# tinyK20.net
KiCad netlist of a schematic drawn in EAGLE
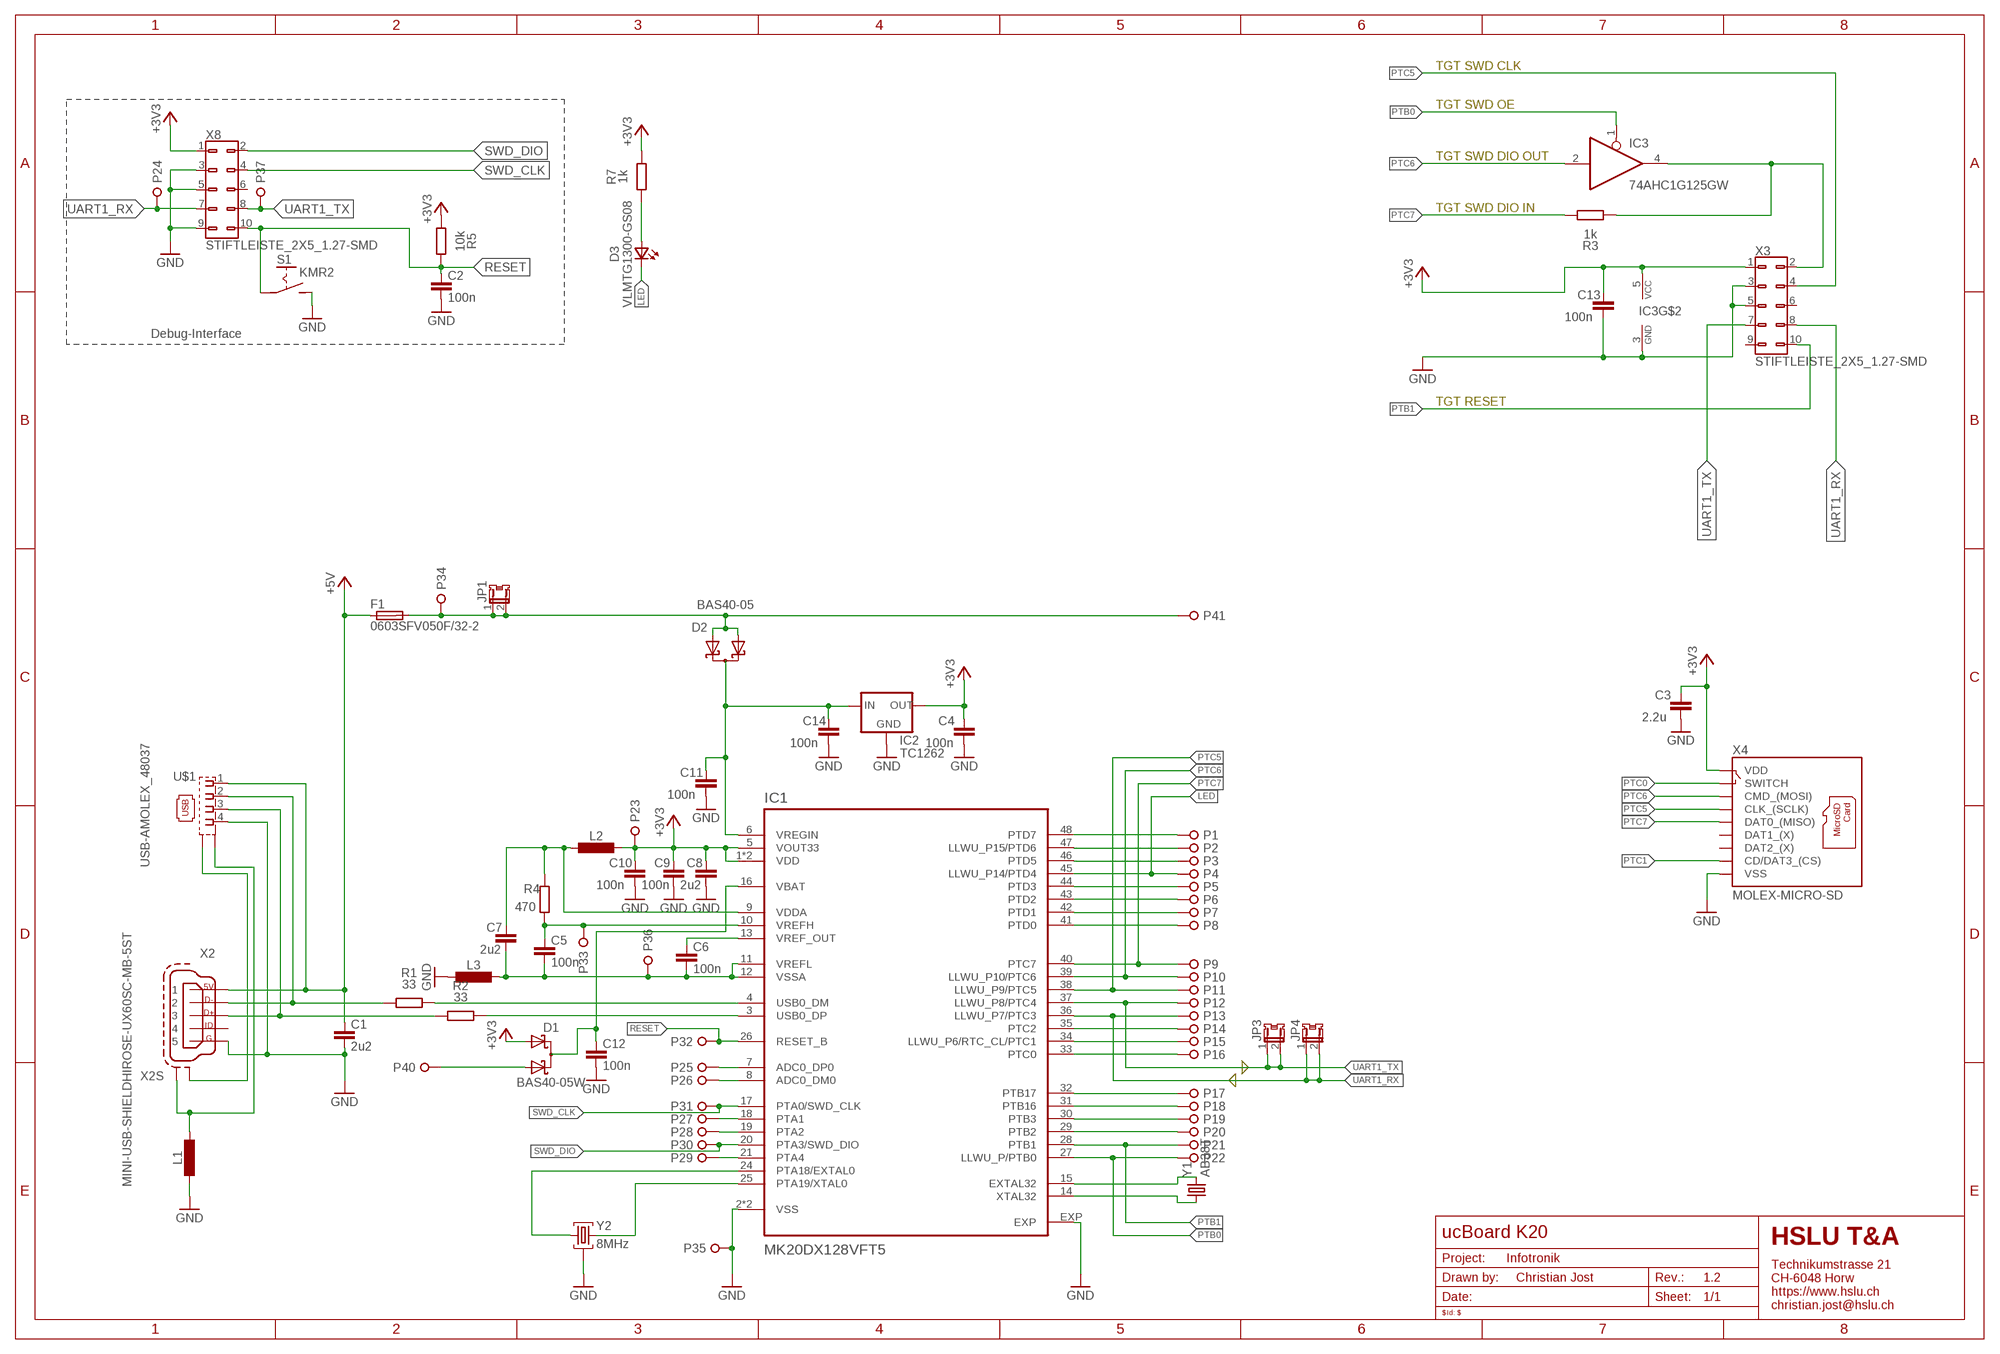
[diagram p0: schematic, sheet 1]

(export (version "E")
  (design (tool "Eeschema 10.0.6"))
  (components
    (comp (ref "C1")
      (value "2u2")
      (footprint "eagle-import:C0603-R")
      (libsource (lib "eagle-import") (part "C0603"))
    )
    (comp (ref "C2")
      (value "100n")
      (footprint "eagle-import:C0603-R")
      (libsource (lib "eagle-import") (part "C0603"))
    )
    (comp (ref "C3")
      (value "2.2u")
      (footprint "eagle-import:C0603-R")
      (libsource (lib "eagle-import") (part "C0603"))
    )
    (comp (ref "C4")
      (value "100n")
      (footprint "eagle-import:C0603-R")
      (libsource (lib "eagle-import") (part "C0603"))
    )
    (comp (ref "C5")
      (value "100n")
      (footprint "eagle-import:C0603-R")
      (libsource (lib "eagle-import") (part "C0603"))
    )
    (comp (ref "C6")
      (value "100n")
      (footprint "eagle-import:C0603-R")
      (libsource (lib "eagle-import") (part "C0603"))
    )
    (comp (ref "C7")
      (value "2u2")
      (footprint "eagle-import:C0603-R")
      (libsource (lib "eagle-import") (part "C0603"))
    )
    (comp (ref "C8")
      (value "2u2")
      (footprint "eagle-import:C0603-R")
      (libsource (lib "eagle-import") (part "C0603"))
    )
    (comp (ref "C9")
      (value "100n")
      (footprint "eagle-import:C0603-R")
      (libsource (lib "eagle-import") (part "C0603"))
    )
    (comp (ref "C10")
      (value "100n")
      (footprint "eagle-import:C0603-R")
      (libsource (lib "eagle-import") (part "C0603"))
    )
    (comp (ref "C11")
      (value "100n")
      (footprint "eagle-import:C0603-R")
      (libsource (lib "eagle-import") (part "C0603"))
    )
    (comp (ref "C12")
      (value "100n")
      (footprint "eagle-import:C0603-R")
      (libsource (lib "eagle-import") (part "C0603"))
    )
    (comp (ref "C13")
      (value "100n")
      (footprint "eagle-import:C0603-R")
      (libsource (lib "eagle-import") (part "C0603"))
    )
    (comp (ref "C14")
      (value "100n")
      (footprint "eagle-import:C0603-R")
      (libsource (lib "eagle-import") (part "C0603"))
    )
    (comp (ref "D1")
      (value "BAS40-05W")
      (footprint "eagle-import:SOT-323")
      (libsource (lib "eagle-import") (part "BAS40-05W"))
    )
    (comp (ref "D2")
      (value "BAS40-05")
      (footprint "eagle-import:SOT-23")
      (libsource (lib "eagle-import") (part "BAS40-05"))
    )
    (comp (ref "D3")
      (value "VLMTG1300-GS08")
      (footprint "eagle-import:D0603-R")
      (libsource (lib "eagle-import") (part "VLMTG1300-GS08"))
    )
    (comp (ref "F1")
      (value "0603SFV050F/32-2")
      (footprint "eagle-import:0603-R")
      (libsource (lib "eagle-import") (part "0603SFVF/32-2050"))
    )
    (comp (ref "IC1")
      (value "MK20DX128VFT5")
      (footprint "eagle-import:QFN48")
      (libsource (lib "eagle-import") (part "MK20DFTX128V?5"))
    )
    (comp (ref "IC2")
      (value "TC1262")
      (footprint "eagle-import:SOT-223")
      (libsource (lib "eagle-import") (part "TC1262"))
    )
    (comp (ref "IC3")
      (value "74AHC1G125GW")
      (footprint "eagle-import:SOT-353")
      (libsource (lib "eagle-import") (part "741G125GWAHC"))
    )
    (comp (ref "JP1")
      (value "JP1-SMD-1.2X1.8")
      (footprint "eagle-import:JP-SMD-1.2X1.8")
      (libsource (lib "eagle-import") (part "JP1-SMD-1.2X1.8"))
    )
    (comp (ref "JP3")
      (value "JP1-SMD-1.2X1.8")
      (footprint "eagle-import:JP-SMD-1.2X1.8")
      (libsource (lib "eagle-import") (part "JP1-SMD-1.2X1.8"))
    )
    (comp (ref "JP4")
      (value "JP1-SMD-1.2X1.8")
      (footprint "eagle-import:JP-SMD-1.2X1.8")
      (libsource (lib "eagle-import") (part "JP1-SMD-1.2X1.8"))
    )
    (comp (ref "L1")
      (value "L")
      (footprint "eagle-import:L0603-R")
      (libsource (lib "eagle-import") (part "L"))
    )
    (comp (ref "L2")
      (value "L")
      (footprint "eagle-import:L0603-R")
      (libsource (lib "eagle-import") (part "L"))
    )
    (comp (ref "L3")
      (value "L")
      (footprint "eagle-import:L0603-R")
      (libsource (lib "eagle-import") (part "L"))
    )
    (comp (ref "P1")
      (value "SOLDERPAD")
      (footprint "eagle-import:SOLDERPAD_TH_0.9")
      (libsource (lib "eagle-import") (part "SOLDERPAD"))
    )
    (comp (ref "P2")
      (value "SOLDERPAD")
      (footprint "eagle-import:SOLDERPAD_TH_0.9")
      (libsource (lib "eagle-import") (part "SOLDERPAD"))
    )
    (comp (ref "P3")
      (value "SOLDERPAD")
      (footprint "eagle-import:SOLDERPAD_TH_0.9")
      (libsource (lib "eagle-import") (part "SOLDERPAD"))
    )
    (comp (ref "P4")
      (value "SOLDERPAD")
      (footprint "eagle-import:SOLDERPAD_TH_0.9")
      (libsource (lib "eagle-import") (part "SOLDERPAD"))
    )
    (comp (ref "P5")
      (value "SOLDERPAD")
      (footprint "eagle-import:SOLDERPAD_TH_0.9")
      (libsource (lib "eagle-import") (part "SOLDERPAD"))
    )
    (comp (ref "P6")
      (value "SOLDERPAD")
      (footprint "eagle-import:SOLDERPAD_TH_0.9")
      (libsource (lib "eagle-import") (part "SOLDERPAD"))
    )
    (comp (ref "P7")
      (value "SOLDERPAD")
      (footprint "eagle-import:SOLDERPAD_TH_0.9")
      (libsource (lib "eagle-import") (part "SOLDERPAD"))
    )
    (comp (ref "P8")
      (value "SOLDERPAD")
      (footprint "eagle-import:SOLDERPAD_TH_0.9")
      (libsource (lib "eagle-import") (part "SOLDERPAD"))
    )
    (comp (ref "P9")
      (value "SOLDERPAD")
      (footprint "eagle-import:SOLDERPAD_TH_0.9")
      (libsource (lib "eagle-import") (part "SOLDERPAD"))
    )
    (comp (ref "P10")
      (value "SOLDERPAD")
      (footprint "eagle-import:SOLDERPAD_TH_0.9")
      (libsource (lib "eagle-import") (part "SOLDERPAD"))
    )
    (comp (ref "P11")
      (value "SOLDERPAD")
      (footprint "eagle-import:SOLDERPAD_TH_0.9")
      (libsource (lib "eagle-import") (part "SOLDERPAD"))
    )
    (comp (ref "P12")
      (value "SOLDERPAD")
      (footprint "eagle-import:SOLDERPAD_TH_0.9")
      (libsource (lib "eagle-import") (part "SOLDERPAD"))
    )
    (comp (ref "P13")
      (value "SOLDERPAD")
      (footprint "eagle-import:SOLDERPAD_TH_0.9")
      (libsource (lib "eagle-import") (part "SOLDERPAD"))
    )
    (comp (ref "P14")
      (value "SOLDERPAD")
      (footprint "eagle-import:SOLDERPAD_TH_0.9")
      (libsource (lib "eagle-import") (part "SOLDERPAD"))
    )
    (comp (ref "P15")
      (value "SOLDERPAD")
      (footprint "eagle-import:SOLDERPAD_TH_0.9")
      (libsource (lib "eagle-import") (part "SOLDERPAD"))
    )
    (comp (ref "P16")
      (value "SOLDERPAD")
      (footprint "eagle-import:SOLDERPAD_TH_0.9")
      (libsource (lib "eagle-import") (part "SOLDERPAD"))
    )
    (comp (ref "P17")
      (value "SOLDERPAD")
      (footprint "eagle-import:SOLDERPAD_TH_0.9")
      (libsource (lib "eagle-import") (part "SOLDERPAD"))
    )
    (comp (ref "P18")
      (value "SOLDERPAD")
      (footprint "eagle-import:SOLDERPAD_TH_0.9")
      (libsource (lib "eagle-import") (part "SOLDERPAD"))
    )
    (comp (ref "P19")
      (value "SOLDERPAD")
      (footprint "eagle-import:SOLDERPAD_TH_0.9")
      (libsource (lib "eagle-import") (part "SOLDERPAD"))
    )
    (comp (ref "P20")
      (value "SOLDERPAD")
      (footprint "eagle-import:SOLDERPAD_TH_0.9")
      (libsource (lib "eagle-import") (part "SOLDERPAD"))
    )
    (comp (ref "P21")
      (value "SOLDERPAD")
      (footprint "eagle-import:SOLDERPAD_TH_0.9")
      (libsource (lib "eagle-import") (part "SOLDERPAD"))
    )
    (comp (ref "P22")
      (value "SOLDERPAD")
      (footprint "eagle-import:SOLDERPAD_TH_0.9")
      (libsource (lib "eagle-import") (part "SOLDERPAD"))
    )
    (comp (ref "P23")
      (value "SOLDERPAD")
      (footprint "eagle-import:SOLDERPAD_TH_0.9")
      (libsource (lib "eagle-import") (part "SOLDERPAD"))
    )
    (comp (ref "P24")
      (value "SOLDERPAD")
      (footprint "eagle-import:SOLDERPAD_TH_0.9")
      (libsource (lib "eagle-import") (part "SOLDERPAD"))
    )
    (comp (ref "P25")
      (value "SOLDERPAD")
      (footprint "eagle-import:SOLDERPAD_TH_0.9")
      (libsource (lib "eagle-import") (part "SOLDERPAD"))
    )
    (comp (ref "P26")
      (value "SOLDERPAD")
      (footprint "eagle-import:SOLDERPAD_TH_0.9")
      (libsource (lib "eagle-import") (part "SOLDERPAD"))
    )
    (comp (ref "P27")
      (value "SOLDERPAD")
      (footprint "eagle-import:SOLDERPAD_TH_0.9")
      (libsource (lib "eagle-import") (part "SOLDERPAD"))
    )
    (comp (ref "P28")
      (value "SOLDERPAD")
      (footprint "eagle-import:SOLDERPAD_TH_0.9")
      (libsource (lib "eagle-import") (part "SOLDERPAD"))
    )
    (comp (ref "P29")
      (value "SOLDERPAD")
      (footprint "eagle-import:SOLDERPAD_TH_0.9")
      (libsource (lib "eagle-import") (part "SOLDERPAD"))
    )
    (comp (ref "P30")
      (value "SOLDERPAD")
      (footprint "eagle-import:SOLDERPAD_TH_0.9")
      (libsource (lib "eagle-import") (part "SOLDERPAD"))
    )
    (comp (ref "P31")
      (value "SOLDERPAD")
      (footprint "eagle-import:SOLDERPAD_TH_0.9")
      (libsource (lib "eagle-import") (part "SOLDERPAD"))
    )
    (comp (ref "P32")
      (value "SOLDERPAD")
      (footprint "eagle-import:SOLDERPAD_TH_0.9")
      (libsource (lib "eagle-import") (part "SOLDERPAD"))
    )
    (comp (ref "P33")
      (value "SOLDERPAD")
      (footprint "eagle-import:SOLDERPAD_TH_0.9")
      (libsource (lib "eagle-import") (part "SOLDERPAD"))
    )
    (comp (ref "P34")
      (value "SOLDERPAD")
      (footprint "eagle-import:SOLDERPAD_TH_0.9")
      (libsource (lib "eagle-import") (part "SOLDERPAD"))
    )
    (comp (ref "P35")
      (value "SOLDERPAD")
      (footprint "eagle-import:SOLDERPAD_TH_0.9")
      (libsource (lib "eagle-import") (part "SOLDERPAD"))
    )
    (comp (ref "P36")
      (value "SOLDERPAD")
      (footprint "eagle-import:SOLDERPAD_TH_0.9")
      (libsource (lib "eagle-import") (part "SOLDERPAD"))
    )
    (comp (ref "P37")
      (value "SOLDERPAD")
      (footprint "eagle-import:SOLDERPAD_TH_0.9")
      (libsource (lib "eagle-import") (part "SOLDERPAD"))
    )
    (comp (ref "P40")
      (value "SOLDERPAD")
      (footprint "eagle-import:SOLDERPAD_TH_0.9")
      (libsource (lib "eagle-import") (part "SOLDERPAD"))
    )
    (comp (ref "P41")
      (value "SOLDERPAD")
      (footprint "eagle-import:SOLDERPAD_TH_0.9")
      (libsource (lib "eagle-import") (part "SOLDERPAD"))
    )
    (comp (ref "R1")
      (value "33")
      (footprint "eagle-import:R0603-R")
      (libsource (lib "eagle-import") (part "R0603"))
    )
    (comp (ref "R2")
      (value "33")
      (footprint "eagle-import:R0603-R")
      (libsource (lib "eagle-import") (part "R0603"))
    )
    (comp (ref "R3")
      (value "1k")
      (footprint "eagle-import:R0603-R")
      (libsource (lib "eagle-import") (part "R0603"))
    )
    (comp (ref "R4")
      (value "470")
      (footprint "eagle-import:R0603-R")
      (libsource (lib "eagle-import") (part "R0603"))
    )
    (comp (ref "R5")
      (value "10k")
      (footprint "eagle-import:R0603-R")
      (libsource (lib "eagle-import") (part "R0603"))
    )
    (comp (ref "R7")
      (value "1k")
      (footprint "eagle-import:R0603-R")
      (libsource (lib "eagle-import") (part "R0603"))
    )
    (comp (ref "S1")
      (value "KMR2")
      (footprint "eagle-import:SWITCH-KMR-SERIES")
      (libsource (lib "eagle-import") (part "KMR211G-LFS"))
    )
    (comp (ref "U$1")
      (value "USB-AMOLEX_48037")
      (footprint "eagle-import:USB-A-MOLEX_48037")
      (libsource (lib "eagle-import") (part "USB-AMOLEX_48037"))
    )
    (comp (ref "X2")
      (value "MINI-USB-SHIELDHIROSE-UX60SC-MB-5ST")
      (footprint "eagle-import:USB-MINI-B-HORIZ_HIROSE-UX60SC-MB-5ST")
      (fields (field (name "MFR") "HIROSE"))
      (libsource (lib "eagle-import") (part "MINI-USB-SHIELDHIROSE-UX60SC-MB-5ST"))
    )
    (comp (ref "X3")
      (value "STIFTLEISTE_2X5_1.27-SMD")
      (footprint "eagle-import:STIFTLEISTE_2X5_1.27_SMD")
      (libsource (lib "eagle-import") (part "STIFTLEISTE_2X5_1.27-SMD"))
    )
    (comp (ref "X4")
      (value "MOLEX-MICRO-SD")
      (footprint "eagle-import:SD-105027-001")
      (libsource (lib "eagle-import") (part "MOLEX-MICRO-SD"))
    )
    (comp (ref "X8")
      (value "STIFTLEISTE_2X5_1.27-SMD")
      (footprint "eagle-import:STIFTLEISTE_2X5_1.27_SMD")
      (libsource (lib "eagle-import") (part "STIFTLEISTE_2X5_1.27-SMD"))
    )
    (comp (ref "Y1")
      (value "AB38T")
      (footprint "eagle-import:CRYSTAL-AB38T")
      (libsource (lib "eagle-import") (part "AB?T38"))
    )
    (comp (ref "Y2")
      (value "8MHz")
      (footprint "eagle-import:CSTCE")
      (libsource (lib "eagle-import") (part "CSTCE8M00G15C"))
    )
  )
  (nets
    (net (code "1") (name "+3V3") (class "Default")
      (node (ref "C10") (pin "1") (pinfunction "1_1") (pintype "passive"))
      (node (ref "C13") (pin "1") (pinfunction "1_1") (pintype "passive"))
      (node (ref "C3") (pin "1") (pinfunction "1_1") (pintype "passive"))
      (node (ref "C4") (pin "1") (pinfunction "1_1") (pintype "passive"))
      (node (ref "C8") (pin "1") (pinfunction "1_1") (pintype "passive"))
      (node (ref "C9") (pin "1") (pinfunction "1_1") (pintype "passive"))
      (node (ref "D1") (pin "1") (pinfunction "A_1") (pintype "passive"))
      (node (ref "IC1") (pin "1") (pinfunction "VDD_1") (pintype "power_in"))
      (node (ref "IC1") (pin "22") (pinfunction "VDD_22") (pintype "power_in"))
      (node (ref "IC1") (pin "5") (pinfunction "VOUT33_5") (pintype "output"))
      (node (ref "IC2") (pin "3") (pinfunction "OUT_3") (pintype "passive"))
      (node (ref "IC3") (pin "5") (pinfunction "VCC_5") (pintype "power_in"))
      (node (ref "L2") (pin "2") (pinfunction "2_2") (pintype "passive"))
      (node (ref "P23") (pin "1") (pinfunction "PAD_1") (pintype "bidirectional"))
      (node (ref "R5") (pin "1") (pinfunction "1_1") (pintype "passive"))
      (node (ref "R7") (pin "2") (pinfunction "2_2") (pintype "passive"))
      (node (ref "X3") (pin "1") (pinfunction "1_1") (pintype "passive"))
      (node (ref "X4") (pin "P4") (pinfunction "VDD_P4") (pintype "passive"))
      (node (ref "X8") (pin "1") (pinfunction "1_1") (pintype "passive"))
    )
    (net (code "2") (name "+5V") (class "Default")
      (node (ref "C1") (pin "1") (pinfunction "1_1") (pintype "passive"))
      (node (ref "F1") (pin "1") (pinfunction "1_1") (pintype "passive"))
      (node (ref "U$1") (pin "1") (pinfunction "1_1") (pintype "passive"))
      (node (ref "X2") (pin "1") (pinfunction "1_1") (pintype "passive"))
    )
    (net (code "3") (name "GND") (class "Default")
      (node (ref "C1") (pin "2") (pinfunction "2_2") (pintype "passive"))
      (node (ref "C10") (pin "2") (pinfunction "2_2") (pintype "passive"))
      (node (ref "C11") (pin "2") (pinfunction "2_2") (pintype "passive"))
      (node (ref "C12") (pin "2") (pinfunction "2_2") (pintype "passive"))
      (node (ref "C13") (pin "2") (pinfunction "2_2") (pintype "passive"))
      (node (ref "C14") (pin "2") (pinfunction "2_2") (pintype "passive"))
      (node (ref "C2") (pin "2") (pinfunction "2_2") (pintype "passive"))
      (node (ref "C3") (pin "2") (pinfunction "2_2") (pintype "passive"))
      (node (ref "C4") (pin "2") (pinfunction "2_2") (pintype "passive"))
      (node (ref "C8") (pin "2") (pinfunction "2_2") (pintype "passive"))
      (node (ref "C9") (pin "2") (pinfunction "2_2") (pintype "passive"))
      (node (ref "IC1") (pin "2") (pinfunction "VSS_2") (pintype "power_in"))
      (node (ref "IC1") (pin "23") (pinfunction "VSS_23") (pintype "power_in"))
      (node (ref "IC1") (pin "EXP") (pinfunction "EXP_EXP") (pintype "bidirectional"))
      (node (ref "IC2") (pin "2") (pinfunction "GND_2") (pintype "input"))
      (node (ref "IC2") (pin "4") (pinfunction "GND_4") (pintype "input"))
      (node (ref "IC3") (pin "3") (pinfunction "GND_3") (pintype "power_in"))
      (node (ref "L1") (pin "1") (pinfunction "1_1") (pintype "passive"))
      (node (ref "L3") (pin "1") (pinfunction "1_1") (pintype "passive"))
      (node (ref "P35") (pin "1") (pinfunction "PAD_1") (pintype "bidirectional"))
      (node (ref "S1") (pin "3") (pinfunction "S_3") (pintype "passive"))
      (node (ref "S1") (pin "4") (pinfunction "S_4") (pintype "passive"))
      (node (ref "U$1") (pin "4") (pinfunction "4_4") (pintype "passive"))
      (node (ref "X2") (pin "5") (pinfunction "5_5") (pintype "passive"))
      (node (ref "X3") (pin "3") (pinfunction "3_3") (pintype "passive"))
      (node (ref "X3") (pin "5") (pinfunction "5_5") (pintype "passive"))
      (node (ref "X4") (pin "P6") (pinfunction "VSS_P6") (pintype "passive"))
      (node (ref "X8") (pin "3") (pinfunction "3_3") (pintype "passive"))
      (node (ref "X8") (pin "5") (pinfunction "5_5") (pintype "passive"))
      (node (ref "X8") (pin "9") (pinfunction "9_9") (pintype "passive"))
      (node (ref "Y2") (pin "2") (pinfunction "2_2") (pintype "passive"))
    )
    (net (code "4") (name "LED") (class "Default")
      (node (ref "D3") (pin "2") (pinfunction "K_2") (pintype "passive"))
      (node (ref "IC1") (pin "45") (pinfunction "LLWU_P14/PTD4_45") (pintype "bidirectional"))
      (node (ref "P4") (pin "1") (pinfunction "PAD_1") (pintype "bidirectional"))
    )
    (net (code "5") (name "Net-(D1B-A)") (class "Default")
      (node (ref "D1") (pin "2") (pinfunction "A_2") (pintype "passive"))
      (node (ref "P40") (pin "1") (pinfunction "PAD_1") (pintype "bidirectional"))
    )
    (net (code "6") (name "Net-(D1C-COMMON)") (class "Default")
      (node (ref "C12") (pin "1") (pinfunction "1_1") (pintype "passive"))
      (node (ref "D1") (pin "3") (pinfunction "COMMON_3") (pintype "passive"))
      (node (ref "IC1") (pin "16") (pinfunction "VBAT_16") (pintype "input"))
    )
    (net (code "7") (name "Net-(D2A-A)") (class "Default")
      (node (ref "D2") (pin "1") (pinfunction "A_1") (pintype "passive"))
      (node (ref "D2") (pin "2") (pinfunction "A_2") (pintype "passive"))
      (node (ref "F1") (pin "2") (pinfunction "2_2") (pintype "passive"))
      (node (ref "JP1") (pin "1") (pinfunction "1_1") (pintype "passive"))
      (node (ref "JP1") (pin "2") (pinfunction "2_2") (pintype "passive"))
      (node (ref "P34") (pin "1") (pinfunction "PAD_1") (pintype "bidirectional"))
      (node (ref "P41") (pin "1") (pinfunction "PAD_1") (pintype "bidirectional"))
    )
    (net (code "8") (name "Net-(D2C-COMMON)") (class "Default")
      (node (ref "C11") (pin "1") (pinfunction "1_1") (pintype "passive"))
      (node (ref "C14") (pin "1") (pinfunction "1_1") (pintype "passive"))
      (node (ref "D2") (pin "3") (pinfunction "COMMON_3") (pintype "passive"))
      (node (ref "IC1") (pin "6") (pinfunction "VREGIN_6") (pintype "input"))
      (node (ref "IC2") (pin "1") (pinfunction "IN_1") (pintype "input"))
    )
    (net (code "9") (name "Net-(D3-A)") (class "Default")
      (node (ref "D3") (pin "1") (pinfunction "A_1") (pintype "passive"))
      (node (ref "R7") (pin "1") (pinfunction "1_1") (pintype "passive"))
    )
    (net (code "10") (name "Net-(IC1-ADC0_DM0)") (class "Default")
      (node (ref "IC1") (pin "8") (pinfunction "ADC0_DM0_8") (pintype "input"))
      (node (ref "P26") (pin "1") (pinfunction "PAD_1") (pintype "bidirectional"))
    )
    (net (code "11") (name "Net-(IC1-ADC0_DP0)") (class "Default")
      (node (ref "IC1") (pin "7") (pinfunction "ADC0_DP0_7") (pintype "input"))
      (node (ref "P25") (pin "1") (pinfunction "PAD_1") (pintype "bidirectional"))
    )
    (net (code "12") (name "Net-(IC1-EXTAL32)") (class "Default")
      (node (ref "IC1") (pin "15") (pinfunction "EXTAL32_15") (pintype "bidirectional"))
      (node (ref "Y1") (pin "2") (pinfunction "3_2") (pintype "passive"))
    )
    (net (code "13") (name "Net-(IC1-LLWU_P15{slash}PTD6)") (class "Default")
      (node (ref "IC1") (pin "47") (pinfunction "LLWU_P15/PTD6_47") (pintype "bidirectional"))
      (node (ref "P2") (pin "1") (pinfunction "PAD_1") (pintype "bidirectional"))
    )
    (net (code "14") (name "Net-(IC1-PTA1)") (class "Default")
      (node (ref "IC1") (pin "18") (pinfunction "PTA1_18") (pintype "bidirectional"))
      (node (ref "P27") (pin "1") (pinfunction "PAD_1") (pintype "bidirectional"))
    )
    (net (code "15") (name "Net-(IC1-PTA2)") (class "Default")
      (node (ref "IC1") (pin "19") (pinfunction "PTA2_19") (pintype "bidirectional"))
      (node (ref "P28") (pin "1") (pinfunction "PAD_1") (pintype "bidirectional"))
    )
    (net (code "16") (name "Net-(IC1-PTA4)") (class "Default")
      (node (ref "IC1") (pin "21") (pinfunction "PTA4_21") (pintype "bidirectional"))
      (node (ref "P29") (pin "1") (pinfunction "PAD_1") (pintype "bidirectional"))
    )
    (net (code "17") (name "Net-(IC1-PTA18{slash}EXTAL0)") (class "Default")
      (node (ref "IC1") (pin "24") (pinfunction "PTA18/EXTAL0_24") (pintype "bidirectional"))
      (node (ref "Y2") (pin "1") (pinfunction "1_1") (pintype "passive"))
    )
    (net (code "18") (name "Net-(IC1-PTA19{slash}XTAL0)") (class "Default")
      (node (ref "IC1") (pin "25") (pinfunction "PTA19/XTAL0_25") (pintype "bidirectional"))
      (node (ref "Y2") (pin "3") (pinfunction "3_3") (pintype "passive"))
    )
    (net (code "19") (name "Net-(IC1-PTB2)") (class "Default")
      (node (ref "IC1") (pin "29") (pinfunction "PTB2_29") (pintype "bidirectional"))
      (node (ref "P20") (pin "1") (pinfunction "PAD_1") (pintype "bidirectional"))
    )
    (net (code "20") (name "Net-(IC1-PTB3)") (class "Default")
      (node (ref "IC1") (pin "30") (pinfunction "PTB3_30") (pintype "bidirectional"))
      (node (ref "P19") (pin "1") (pinfunction "PAD_1") (pintype "bidirectional"))
    )
    (net (code "21") (name "Net-(IC1-PTB16)") (class "Default")
      (node (ref "IC1") (pin "31") (pinfunction "PTB16_31") (pintype "bidirectional"))
      (node (ref "P18") (pin "1") (pinfunction "PAD_1") (pintype "bidirectional"))
    )
    (net (code "22") (name "Net-(IC1-PTB17)") (class "Default")
      (node (ref "IC1") (pin "32") (pinfunction "PTB17_32") (pintype "bidirectional"))
      (node (ref "P17") (pin "1") (pinfunction "PAD_1") (pintype "bidirectional"))
    )
    (net (code "23") (name "Net-(IC1-PTC2)") (class "Default")
      (node (ref "IC1") (pin "35") (pinfunction "PTC2_35") (pintype "bidirectional"))
      (node (ref "P14") (pin "1") (pinfunction "PAD_1") (pintype "bidirectional"))
    )
    (net (code "24") (name "Net-(IC1-PTD0)") (class "Default")
      (node (ref "IC1") (pin "41") (pinfunction "PTD0_41") (pintype "bidirectional"))
      (node (ref "P8") (pin "1") (pinfunction "PAD_1") (pintype "bidirectional"))
    )
    (net (code "25") (name "Net-(IC1-PTD1)") (class "Default")
      (node (ref "IC1") (pin "42") (pinfunction "PTD1_42") (pintype "bidirectional"))
      (node (ref "P7") (pin "1") (pinfunction "PAD_1") (pintype "bidirectional"))
    )
    (net (code "26") (name "Net-(IC1-PTD2)") (class "Default")
      (node (ref "IC1") (pin "43") (pinfunction "PTD2_43") (pintype "bidirectional"))
      (node (ref "P6") (pin "1") (pinfunction "PAD_1") (pintype "bidirectional"))
    )
    (net (code "27") (name "Net-(IC1-PTD3)") (class "Default")
      (node (ref "IC1") (pin "44") (pinfunction "PTD3_44") (pintype "bidirectional"))
      (node (ref "P5") (pin "1") (pinfunction "PAD_1") (pintype "bidirectional"))
    )
    (net (code "28") (name "Net-(IC1-PTD5)") (class "Default")
      (node (ref "IC1") (pin "46") (pinfunction "PTD5_46") (pintype "bidirectional"))
      (node (ref "P3") (pin "1") (pinfunction "PAD_1") (pintype "bidirectional"))
    )
    (net (code "29") (name "Net-(IC1-PTD7)") (class "Default")
      (node (ref "IC1") (pin "48") (pinfunction "PTD7_48") (pintype "bidirectional"))
      (node (ref "P1") (pin "1") (pinfunction "PAD_1") (pintype "bidirectional"))
    )
    (net (code "30") (name "Net-(IC1-USB0_DM)") (class "Default")
      (node (ref "IC1") (pin "4") (pinfunction "USB0_DM_4") (pintype "input"))
      (node (ref "R1") (pin "2") (pinfunction "2_2") (pintype "passive"))
    )
    (net (code "31") (name "Net-(IC1-USB0_DP)") (class "Default")
      (node (ref "IC1") (pin "3") (pinfunction "USB0_DP_3") (pintype "input"))
      (node (ref "R2") (pin "2") (pinfunction "2_2") (pintype "passive"))
    )
    (net (code "32") (name "Net-(IC1-VDDA)") (class "Default")
      (node (ref "C7") (pin "1") (pinfunction "1_1") (pintype "passive"))
      (node (ref "IC1") (pin "9") (pinfunction "VDDA_9") (pintype "power_in"))
      (node (ref "L2") (pin "1") (pinfunction "1_1") (pintype "passive"))
      (node (ref "R4") (pin "2") (pinfunction "2_2") (pintype "passive"))
    )
    (net (code "33") (name "Net-(IC1-VREFH)") (class "Default")
      (node (ref "C5") (pin "1") (pinfunction "1_1") (pintype "passive"))
      (node (ref "IC1") (pin "10") (pinfunction "VREFH_10") (pintype "input"))
      (node (ref "P33") (pin "1") (pinfunction "PAD_1") (pintype "bidirectional"))
      (node (ref "R4") (pin "1") (pinfunction "1_1") (pintype "passive"))
    )
    (net (code "34") (name "Net-(IC1-VREFL)") (class "Default")
      (node (ref "C5") (pin "2") (pinfunction "2_2") (pintype "passive"))
      (node (ref "C6") (pin "2") (pinfunction "2_2") (pintype "passive"))
      (node (ref "C7") (pin "2") (pinfunction "2_2") (pintype "passive"))
      (node (ref "IC1") (pin "11") (pinfunction "VREFL_11") (pintype "input"))
      (node (ref "IC1") (pin "12") (pinfunction "VSSA_12") (pintype "input"))
      (node (ref "L3") (pin "2") (pinfunction "2_2") (pintype "passive"))
      (node (ref "P36") (pin "1") (pinfunction "PAD_1") (pintype "bidirectional"))
    )
    (net (code "35") (name "Net-(IC1-VREF_OUT)") (class "Default")
      (node (ref "C6") (pin "1") (pinfunction "1_1") (pintype "passive"))
      (node (ref "IC1") (pin "13") (pinfunction "VREF_OUT_13") (pintype "output"))
    )
    (net (code "36") (name "Net-(IC1-XTAL32)") (class "Default")
      (node (ref "IC1") (pin "14") (pinfunction "XTAL32_14") (pintype "bidirectional"))
      (node (ref "Y1") (pin "1") (pinfunction "1_1") (pintype "passive"))
    )
    (net (code "37") (name "Net-(IC3A-O)") (class "Default")
      (node (ref "IC3") (pin "4") (pinfunction "O_4") (pintype "tri_state"))
      (node (ref "R3") (pin "1") (pinfunction "1_1") (pintype "passive"))
      (node (ref "X3") (pin "2") (pinfunction "2_2") (pintype "passive"))
    )
    (net (code "38") (name "Net-(L1-Pad2)") (class "Default")
      (node (ref "L1") (pin "2") (pinfunction "2_2") (pintype "passive"))
      (node (ref "U$1") (pin "S1A") (pinfunction "S1_S1A") (pintype "passive"))
      (node (ref "U$1") (pin "S1B") (pinfunction "S1_S1B") (pintype "passive"))
      (node (ref "X2") (pin "S2") (pinfunction "S2_S2") (pintype "passive"))
    )
    (net (code "39") (name "Net-(R1-Pad1)") (class "Default")
      (node (ref "R1") (pin "1") (pinfunction "1_1") (pintype "passive"))
      (node (ref "U$1") (pin "2") (pinfunction "2_2") (pintype "passive"))
      (node (ref "X2") (pin "2") (pinfunction "2_2") (pintype "passive"))
    )
    (net (code "40") (name "Net-(R2-Pad1)") (class "Default")
      (node (ref "R2") (pin "1") (pinfunction "1_1") (pintype "passive"))
      (node (ref "U$1") (pin "3") (pinfunction "3_3") (pintype "passive"))
      (node (ref "X2") (pin "3") (pinfunction "3_3") (pintype "passive"))
    )
    (net (code "41") (name "Net-(U$1-S2-PadS2A)") (class "Default")
      (node (ref "U$1") (pin "S2A") (pinfunction "S2_S2A") (pintype "passive"))
      (node (ref "U$1") (pin "S2B") (pinfunction "S2_S2B") (pintype "passive"))
      (node (ref "X2") (pin "S1") (pinfunction "S1_S1") (pintype "passive"))
    )
    (net (code "42") (name "PTB0") (class "Default")
      (node (ref "IC1") (pin "27") (pinfunction "LLWU_P/PTB0_27") (pintype "bidirectional"))
      (node (ref "IC3") (pin "1") (pinfunction "OE_1") (pintype "input"))
      (node (ref "P22") (pin "1") (pinfunction "PAD_1") (pintype "bidirectional"))
    )
    (net (code "43") (name "PTB1") (class "Default")
      (node (ref "IC1") (pin "28") (pinfunction "PTB1_28") (pintype "bidirectional"))
      (node (ref "P21") (pin "1") (pinfunction "PAD_1") (pintype "bidirectional"))
      (node (ref "X3") (pin "10") (pinfunction "10_10") (pintype "passive"))
    )
    (net (code "44") (name "PTC0") (class "Default")
      (node (ref "IC1") (pin "33") (pinfunction "PTC0_33") (pintype "bidirectional"))
      (node (ref "P16") (pin "1") (pinfunction "PAD_1") (pintype "bidirectional"))
      (node (ref "X4") (pin "G1") (pinfunction "SWITCH_G1") (pintype "passive"))
    )
    (net (code "45") (name "PTC1") (class "Default")
      (node (ref "IC1") (pin "34") (pinfunction "LLWU_P6/RTC_CL/PTC1_34") (pintype "bidirectional"))
      (node (ref "P15") (pin "1") (pinfunction "PAD_1") (pintype "bidirectional"))
      (node (ref "X4") (pin "P2") (pinfunction "CD/DAT3_(CS)_P2") (pintype "passive"))
    )
    (net (code "46") (name "PTC5") (class "Default")
      (node (ref "IC1") (pin "38") (pinfunction "LLWU_P9/PTC5_38") (pintype "bidirectional"))
      (node (ref "P11") (pin "1") (pinfunction "PAD_1") (pintype "bidirectional"))
      (node (ref "X3") (pin "4") (pinfunction "4_4") (pintype "passive"))
      (node (ref "X4") (pin "P5") (pinfunction "CLK_(SCLK)_P5") (pintype "passive"))
    )
    (net (code "47") (name "PTC6") (class "Default")
      (node (ref "IC1") (pin "39") (pinfunction "LLWU_P10/PTC6_39") (pintype "bidirectional"))
      (node (ref "IC3") (pin "2") (pinfunction "I_2") (pintype "input"))
      (node (ref "P10") (pin "1") (pinfunction "PAD_1") (pintype "bidirectional"))
      (node (ref "X4") (pin "P3") (pinfunction "CMD_(MOSI)_P3") (pintype "passive"))
    )
    (net (code "48") (name "PTC7") (class "Default")
      (node (ref "IC1") (pin "40") (pinfunction "PTC7_40") (pintype "bidirectional"))
      (node (ref "P9") (pin "1") (pinfunction "PAD_1") (pintype "bidirectional"))
      (node (ref "R3") (pin "2") (pinfunction "2_2") (pintype "passive"))
      (node (ref "X4") (pin "P7") (pinfunction "DAT0_(MISO)_P7") (pintype "passive"))
    )
    (net (code "49") (name "RESET") (class "Default")
      (node (ref "C2") (pin "1") (pinfunction "1_1") (pintype "passive"))
      (node (ref "IC1") (pin "26") (pinfunction "RESET_B_26") (pintype "input"))
      (node (ref "P32") (pin "1") (pinfunction "PAD_1") (pintype "bidirectional"))
      (node (ref "R5") (pin "2") (pinfunction "2_2") (pintype "passive"))
      (node (ref "S1") (pin "1") (pinfunction "C_1") (pintype "passive"))
      (node (ref "S1") (pin "2") (pinfunction "C_2") (pintype "passive"))
      (node (ref "X8") (pin "10") (pinfunction "10_10") (pintype "passive"))
    )
    (net (code "50") (name "SWD_CLK") (class "Default")
      (node (ref "IC1") (pin "17") (pinfunction "PTA0/SWD_CLK_17") (pintype "bidirectional"))
      (node (ref "P31") (pin "1") (pinfunction "PAD_1") (pintype "bidirectional"))
      (node (ref "X8") (pin "4") (pinfunction "4_4") (pintype "passive"))
    )
    (net (code "51") (name "SWD_DIO") (class "Default")
      (node (ref "IC1") (pin "20") (pinfunction "PTA3/SWD_DIO_20") (pintype "bidirectional"))
      (node (ref "P30") (pin "1") (pinfunction "PAD_1") (pintype "bidirectional"))
      (node (ref "X8") (pin "2") (pinfunction "2_2") (pintype "passive"))
    )
    (net (code "52") (name "UART1_RX") (class "Default")
      (node (ref "IC1") (pin "36") (pinfunction "LLWU_P7/PTC3_36") (pintype "bidirectional"))
      (node (ref "JP4") (pin "1") (pinfunction "1_1") (pintype "passive"))
      (node (ref "JP4") (pin "2") (pinfunction "2_2") (pintype "passive"))
      (node (ref "P13") (pin "1") (pinfunction "PAD_1") (pintype "bidirectional"))
      (node (ref "P24") (pin "1") (pinfunction "PAD_1") (pintype "bidirectional"))
      (node (ref "X3") (pin "8") (pinfunction "8_8") (pintype "passive"))
      (node (ref "X8") (pin "7") (pinfunction "7_7") (pintype "passive"))
    )
    (net (code "53") (name "UART1_TX") (class "Default")
      (node (ref "IC1") (pin "37") (pinfunction "LLWU_P8/PTC4_37") (pintype "bidirectional"))
      (node (ref "JP3") (pin "1") (pinfunction "1_1") (pintype "passive"))
      (node (ref "JP3") (pin "2") (pinfunction "2_2") (pintype "passive"))
      (node (ref "P12") (pin "1") (pinfunction "PAD_1") (pintype "bidirectional"))
      (node (ref "P37") (pin "1") (pinfunction "PAD_1") (pintype "bidirectional"))
      (node (ref "X3") (pin "7") (pinfunction "7_7") (pintype "passive"))
      (node (ref "X8") (pin "8") (pinfunction "8_8") (pintype "passive"))
    )
    (net (code "54") (name "unconnected-(X2-Pad4)") (class "Default")
      (node (ref "X2") (pin "4") (pinfunction "4_4") (pintype "passive"))
    )
    (net (code "55") (name "unconnected-(X3-Pad6)") (class "Default")
      (node (ref "X3") (pin "6") (pinfunction "6_6") (pintype "passive"))
    )
    (net (code "56") (name "unconnected-(X3-Pad9)") (class "Default")
      (node (ref "X3") (pin "9") (pinfunction "9_9") (pintype "passive"))
    )
    (net (code "57") (name "unconnected-(X4-DAT1_(X)-PadP8)") (class "Default")
      (node (ref "X4") (pin "P8") (pinfunction "DAT1_(X)_P8") (pintype "passive"))
    )
    (net (code "58") (name "unconnected-(X4-DAT2_(X)-PadP1)") (class "Default")
      (node (ref "X4") (pin "P1") (pinfunction "DAT2_(X)_P1") (pintype "passive"))
    )
    (net (code "59") (name "unconnected-(X8-Pad6)") (class "Default")
      (node (ref "X8") (pin "6") (pinfunction "6_6") (pintype "passive"))
    )
  )
)
